# design.net
KiCad netlist of a schematic drawn in EAGLE
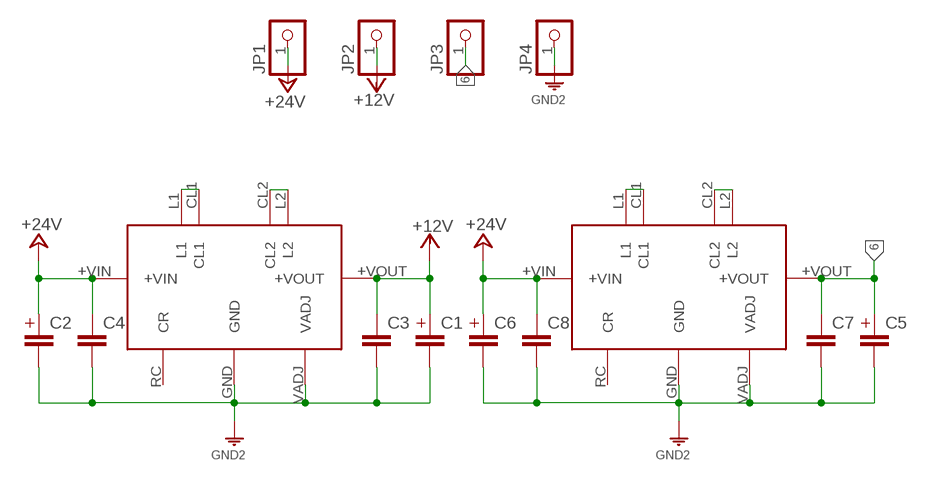
[diagram p0: schematic, sheet 1]

(export (version "E")
  (design (tool "Eeschema 10.0.6"))
  (components
    (comp (ref "C1")
      (value "CAPACITOR-1U")
      (footprint "eagle-import:C_1U")
      (libsource (lib "eagle-import") (part "CAPACITOR-1U"))
    )
    (comp (ref "C2")
      (value "CAPACITOR-1U")
      (footprint "eagle-import:C_1U")
      (libsource (lib "eagle-import") (part "CAPACITOR-1U"))
    )
    (comp (ref "C3")
      (value "MLCC-5")
      (footprint "eagle-import:MLCC_50")
      (libsource (lib "eagle-import") (part "MLCC-5"))
    )
    (comp (ref "C4")
      (value "MLCC-5")
      (footprint "eagle-import:MLCC_50")
      (libsource (lib "eagle-import") (part "MLCC-5"))
    )
    (comp (ref "C5")
      (value "CAPACITOR-1U")
      (footprint "eagle-import:C_1U")
      (libsource (lib "eagle-import") (part "CAPACITOR-1U"))
    )
    (comp (ref "C6")
      (value "CAPACITOR-1U")
      (footprint "eagle-import:C_1U")
      (libsource (lib "eagle-import") (part "CAPACITOR-1U"))
    )
    (comp (ref "C7")
      (value "MLCC-5")
      (footprint "eagle-import:MLCC_50")
      (libsource (lib "eagle-import") (part "MLCC-5"))
    )
    (comp (ref "C8")
      (value "MLCC-5")
      (footprint "eagle-import:MLCC_50")
      (libsource (lib "eagle-import") (part "MLCC-5"))
    )
    (comp (ref "JP1")
      (value "PINHD-1X1")
      (footprint "eagle-import:1X01")
      (libsource (lib "eagle-import") (part "PINHD-1X1"))
    )
    (comp (ref "JP2")
      (value "PINHD-1X1")
      (footprint "eagle-import:1X01")
      (libsource (lib "eagle-import") (part "PINHD-1X1"))
    )
    (comp (ref "JP3")
      (value "PINHD-1X1")
      (footprint "eagle-import:1X01")
      (libsource (lib "eagle-import") (part "PINHD-1X1"))
    )
    (comp (ref "JP4")
      (value "PINHD-1X1")
      (footprint "eagle-import:1X01")
      (libsource (lib "eagle-import") (part "PINHD-1X1"))
    )
    (comp (ref "U$1")
      (value "HPH12002M")
      (footprint "eagle-import:HPH12002M")
      (libsource (lib "eagle-import") (part "HPH12002M"))
    )
    (comp (ref "U$4")
      (value "HPH12002M")
      (footprint "eagle-import:HPH12002M")
      (libsource (lib "eagle-import") (part "HPH12002M"))
    )
  )
  (nets
    (net (code "1") (name "+12V") (class "Default")
      (node (ref "C1") (pin "P$1") (pinfunction "1_P$1") (pintype "passive"))
      (node (ref "C3") (pin "1") (pinfunction "1_1") (pintype "passive"))
      (node (ref "JP2") (pin "1") (pinfunction "1_1") (pintype "passive"))
      (node (ref "U$1") (pin "+VOUT") (pinfunction "+VOUT_+VOUT") (pintype "bidirectional"))
    )
    (net (code "2") (name "+24V") (class "Default")
      (node (ref "C2") (pin "P$1") (pinfunction "1_P$1") (pintype "passive"))
      (node (ref "C4") (pin "1") (pinfunction "1_1") (pintype "passive"))
      (node (ref "C6") (pin "P$1") (pinfunction "1_P$1") (pintype "passive"))
      (node (ref "C8") (pin "1") (pinfunction "1_1") (pintype "passive"))
      (node (ref "JP1") (pin "1") (pinfunction "1_1") (pintype "passive"))
      (node (ref "U$1") (pin "+VIN") (pinfunction "+VIN_+VIN") (pintype "bidirectional"))
      (node (ref "U$4") (pin "+VIN") (pinfunction "+VIN_+VIN") (pintype "bidirectional"))
    )
    (net (code "3") (name "6") (class "Default")
      (node (ref "C5") (pin "P$1") (pinfunction "1_P$1") (pintype "passive"))
      (node (ref "C7") (pin "1") (pinfunction "1_1") (pintype "passive"))
      (node (ref "JP3") (pin "1") (pinfunction "1_1") (pintype "passive"))
      (node (ref "U$4") (pin "+VOUT") (pinfunction "+VOUT_+VOUT") (pintype "bidirectional"))
    )
    (net (code "4") (name "GND2") (class "Default")
      (node (ref "C1") (pin "P$2") (pinfunction "2_P$2") (pintype "passive"))
      (node (ref "C2") (pin "P$2") (pinfunction "2_P$2") (pintype "passive"))
      (node (ref "C3") (pin "2") (pinfunction "2_2") (pintype "passive"))
      (node (ref "C4") (pin "2") (pinfunction "2_2") (pintype "passive"))
      (node (ref "C5") (pin "P$2") (pinfunction "2_P$2") (pintype "passive"))
      (node (ref "C6") (pin "P$2") (pinfunction "2_P$2") (pintype "passive"))
      (node (ref "C7") (pin "2") (pinfunction "2_2") (pintype "passive"))
      (node (ref "C8") (pin "2") (pinfunction "2_2") (pintype "passive"))
      (node (ref "JP4") (pin "1") (pinfunction "1_1") (pintype "passive"))
      (node (ref "U$1") (pin "GND") (pinfunction "GND_GND") (pintype "bidirectional"))
      (node (ref "U$1") (pin "VADJ") (pinfunction "VADJ_VADJ") (pintype "bidirectional"))
      (node (ref "U$4") (pin "GND") (pinfunction "GND_GND") (pintype "bidirectional"))
      (node (ref "U$4") (pin "VADJ") (pinfunction "VADJ_VADJ") (pintype "bidirectional"))
    )
    (net (code "5") (name "Net-(U$1-PadCL1)") (class "Default")
      (node (ref "U$1") (pin "CL1") (pinfunction "CL1_CL1") (pintype "bidirectional"))
      (node (ref "U$1") (pin "L1") (pinfunction "L1_L1") (pintype "bidirectional"))
    )
    (net (code "6") (name "Net-(U$1-PadCL2)") (class "Default")
      (node (ref "U$1") (pin "CL2") (pinfunction "CL2_CL2") (pintype "bidirectional"))
      (node (ref "U$1") (pin "L2") (pinfunction "L2_L2") (pintype "bidirectional"))
    )
    (net (code "7") (name "Net-(U$4-PadCL1)") (class "Default")
      (node (ref "U$4") (pin "CL1") (pinfunction "CL1_CL1") (pintype "bidirectional"))
      (node (ref "U$4") (pin "L1") (pinfunction "L1_L1") (pintype "bidirectional"))
    )
    (net (code "8") (name "Net-(U$4-PadCL2)") (class "Default")
      (node (ref "U$4") (pin "CL2") (pinfunction "CL2_CL2") (pintype "bidirectional"))
      (node (ref "U$4") (pin "L2") (pinfunction "L2_L2") (pintype "bidirectional"))
    )
    (net (code "9") (name "unconnected-(U$1-CR-PadRC)") (class "Default")
      (node (ref "U$1") (pin "RC") (pinfunction "CR_RC") (pintype "bidirectional"))
    )
    (net (code "10") (name "unconnected-(U$4-CR-PadRC)") (class "Default")
      (node (ref "U$4") (pin "RC") (pinfunction "CR_RC") (pintype "bidirectional"))
    )
  )
)
